# p4b-power.net
KiCad netlist of a schematic drawn in Altium Designer
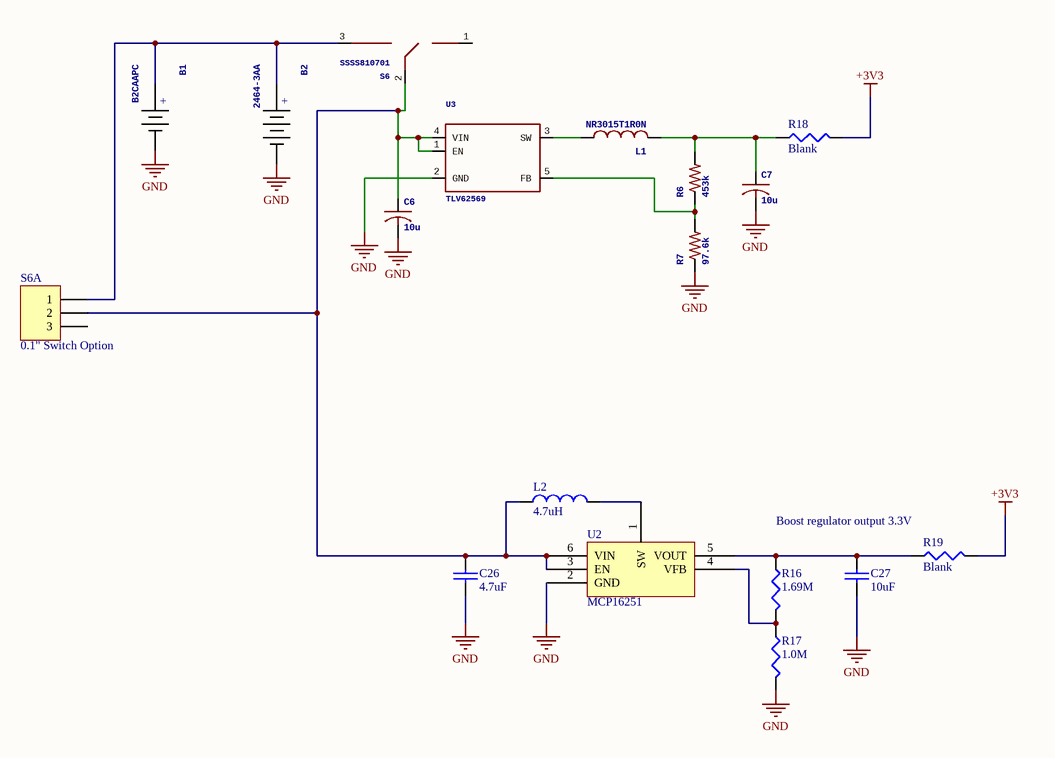
[diagram p0: p4b-power.SchDoc]

(export (version "E")
  (design (tool "Eeschema 10.0.6"))
  (components
    (comp (ref "B1")
      (value "B2CAAPC")
      (footprint "bdk-pcblib:B2CAAPC")
      (libsource (lib "bdk-schlib") (part "B2CAAPC"))
    )
    (comp (ref "B2")
      (value "2464-3AA")
      (footprint "2464-3AA")
      (libsource (lib "bdk-schlib") (part "2464-3AA"))
    )
    (comp (ref "C6")
      (value "10u")
      (footprint "C0805")
      (description "CAPACITOR, American symbol")
      (fields (field (name "MPN") "JMK212BJ106KD-T"))
      (libsource (lib "rcl") (part "C-USC0805K"))
    )
    (comp (ref "C7")
      (value "10u")
      (footprint "C0805")
      (description "CAPACITOR, American symbol")
      (fields (field (name "MPN") "JMK212BJ106KD-T"))
      (libsource (lib "rcl") (part "C-USC0805K"))
    )
    (comp (ref "C26")
      (value "4.7uF")
      (footprint "C0805")
      (description "CAP, CER, 4.7UF, 6.3v, 10%, X5R, 0805")
      (fields (field (name "Comment") "VALUE"))
      (libsource (lib "bdk-schlib") (part "CAP-4.7UF-0805"))
    )
    (comp (ref "C27")
      (value "10uF")
      (footprint "C0805")
      (description "CAP, CER, 10UF, 6.3v, 10%, X5R, 0805")
      (fields (field (name "Comment") "VALUE"))
      (libsource (lib "bdk-schlib") (part "CAP-10UF-0805"))
    )
    (comp (ref "L1") (value "NR3015T1R0N") (footprint "NR3015") (libsource (lib "badge") (part "NR3015")))
    (comp (ref "L2")
      (value "4.7uH")
      (footprint "WURTH-WE-TOC-2.8X2.8")
      (description "IND, 4.7UH, SMD")
      (fields (field (name "MFG") "Wurth"))
      (libsource (lib "bdk-schlib") (part "IND-4.7UH-SMD-2.8X2.8"))
    )
    (comp (ref "R6")
      (value "453k")
      (footprint "R0603")
      (description "RESISTOR, American symbol")
      (libsource (lib "rcl") (part "R-US_R0603"))
    )
    (comp (ref "R7")
      (value "97.6k")
      (footprint "R0603")
      (description "RESISTOR, American symbol")
      (libsource (lib "rcl") (part "R-US_R0603"))
    )
    (comp (ref "R16")
      (value "1.69M")
      (footprint "R0603")
      (description "RES, 1.69M, 1/10W, 1%, 0603 SMD")
      (libsource (lib "bdk-schlib") (part "RES-1.69M-0603"))
    )
    (comp (ref "R17")
      (value "1.0M")
      (footprint "R0603")
      (description "RES, 1.0M, 1/10W, 1%, 0603 SMD")
      (libsource (lib "bdk-schlib") (part "RES-1.0M-0603"))
    )
    (comp (ref "R18")
      (value "Blank")
      (footprint "R0603")
      (description "RES, BLANK OHM, 1/10W, 1%, 0603 SMD")
      (libsource (lib "phantron-discretes") (part "RES, BLANK, 0603"))
    )
    (comp (ref "R19")
      (value "Blank")
      (footprint "R0603")
      (description "RES, BLANK OHM, 1/10W, 1%, 0603 SMD")
      (libsource (lib "phantron-discretes") (part "RES, BLANK, 0603"))
    )
    (comp (ref "S6")
      (value "SSSS810701")
      (footprint "SSSS810701")
      (libsource (lib "badge") (part "SSSS810701"))
    )
    (comp (ref "S6A")
      (value "0.1\" Switch Option")
      (footprint "HDR1X3")
      (description "Header, 3-Pin")
      (fields (field (name "PUBLISHER") "Altium Limited"))
      (libsource (lib "Miscellaneous Connectors") (part "Header 3"))
    )
    (comp (ref "U2")
      (value "MCP16251")
      (footprint "SOT23-6")
      (description "MCP16251, IC REG, BST 0.65A")
      (fields (field (name "MFG") "Microchip"))
      (libsource (lib "bdk-schlib") (part "MCP16251-SOT23-6"))
    )
    (comp (ref "U3") (value "TLV62569") (footprint "DBV-5") (libsource (lib "badge") (part "TLV62569")))
  )
  (nets
    (net (code "1") (name "+3V3") (class "Default")
      (node (ref "R18") (pin "2") (pinfunction "B_2") (pintype "passive"))
      (node (ref "R19") (pin "2") (pinfunction "B_2") (pintype "passive"))
    )
    (net (code "2") (name "GND") (class "Default")
      (node (ref "B1") (pin "2") (pinfunction "GND_2") (pintype "passive"))
      (node (ref "B2") (pin "2") (pinfunction "GND_2") (pintype "passive"))
      (node (ref "C26") (pin "2") (pinfunction "B_2") (pintype "passive"))
      (node (ref "C27") (pin "2") (pinfunction "B_2") (pintype "passive"))
      (node (ref "C6") (pin "2") (pinfunction "2_2") (pintype "passive"))
      (node (ref "C7") (pin "2") (pinfunction "2_2") (pintype "passive"))
      (node (ref "R17") (pin "2") (pinfunction "B_2") (pintype "passive"))
      (node (ref "R7") (pin "1") (pinfunction "1_1") (pintype "passive"))
      (node (ref "U2") (pin "2") (pinfunction "GND_2") (pintype "passive"))
      (node (ref "U3") (pin "2") (pinfunction "GND_2") (pintype "passive"))
    )
    (net (code "3") (name "Net-(B1-POS)") (class "Default")
      (node (ref "B1") (pin "1") (pinfunction "POS_1") (pintype "passive"))
      (node (ref "B2") (pin "1") (pinfunction "POS_1") (pintype "passive"))
      (node (ref "S6") (pin "3") (pinfunction "3_3") (pintype "passive"))
      (node (ref "S6A") (pin "1") (pinfunction "1_1") (pintype "passive"))
    )
    (net (code "4") (name "Net-(C26-A)") (class "Default")
      (node (ref "C26") (pin "1") (pinfunction "A_1") (pintype "passive"))
      (node (ref "C6") (pin "1") (pinfunction "1_1") (pintype "passive"))
      (node (ref "L2") (pin "1") (pinfunction "1_1") (pintype "passive"))
      (node (ref "S6") (pin "2") (pinfunction "2_2") (pintype "passive"))
      (node (ref "S6A") (pin "2") (pinfunction "2_2") (pintype "passive"))
      (node (ref "U2") (pin "3") (pinfunction "EN_3") (pintype "passive"))
      (node (ref "U2") (pin "6") (pinfunction "VIN_6") (pintype "passive"))
      (node (ref "U3") (pin "1") (pinfunction "EN_1") (pintype "passive"))
      (node (ref "U3") (pin "4") (pinfunction "VIN_4") (pintype "passive"))
    )
    (net (code "5") (name "Net-(C27-A)") (class "Default")
      (node (ref "C27") (pin "1") (pinfunction "A_1") (pintype "passive"))
      (node (ref "R16") (pin "1") (pinfunction "A_1") (pintype "passive"))
      (node (ref "R19") (pin "1") (pinfunction "A_1") (pintype "passive"))
      (node (ref "U2") (pin "5") (pinfunction "VOUT_5") (pintype "passive"))
    )
    (net (code "6") (name "Net-(R16-B)") (class "Default")
      (node (ref "R16") (pin "2") (pinfunction "B_2") (pintype "passive"))
      (node (ref "R17") (pin "1") (pinfunction "A_1") (pintype "passive"))
      (node (ref "U2") (pin "4") (pinfunction "VFB_4") (pintype "passive"))
    )
    (net (code "7") (name "Net-(R18-A)") (class "Default")
      (node (ref "C7") (pin "1") (pinfunction "1_1") (pintype "passive"))
      (node (ref "L1") (pin "2") (pinfunction "2_2") (pintype "passive"))
      (node (ref "R18") (pin "1") (pinfunction "A_1") (pintype "passive"))
      (node (ref "R6") (pin "2") (pinfunction "2_2") (pintype "passive"))
    )
    (net (code "8") (name "Net-(U2-SW)") (class "Default")
      (node (ref "L2") (pin "2") (pinfunction "2_2") (pintype "passive"))
      (node (ref "U2") (pin "1") (pinfunction "SW_1") (pintype "passive"))
    )
    (net (code "9") (name "Net-(U3-FB)") (class "Default")
      (node (ref "R6") (pin "1") (pinfunction "1_1") (pintype "passive"))
      (node (ref "R7") (pin "2") (pinfunction "2_2") (pintype "passive"))
      (node (ref "U3") (pin "5") (pinfunction "FB_5") (pintype "passive"))
    )
    (net (code "10") (name "Net-(U3-SW)") (class "Default")
      (node (ref "L1") (pin "1") (pinfunction "1_1") (pintype "passive"))
      (node (ref "U3") (pin "3") (pinfunction "SW_3") (pintype "passive"))
    )
    (net (code "11") (name "unconnected-(S6-Pad1)") (class "Default")
      (node (ref "S6") (pin "1") (pinfunction "1_1") (pintype "passive"))
    )
    (net (code "12") (name "unconnected-(S6A-Pad3)") (class "Default")
      (node (ref "S6A") (pin "3") (pinfunction "3_3") (pintype "passive"))
    )
  )
)
